# OGX360I-4CH_-_Middle_Man_P3_-_P4.net
KiCad netlist of a schematic drawn in EAGLE
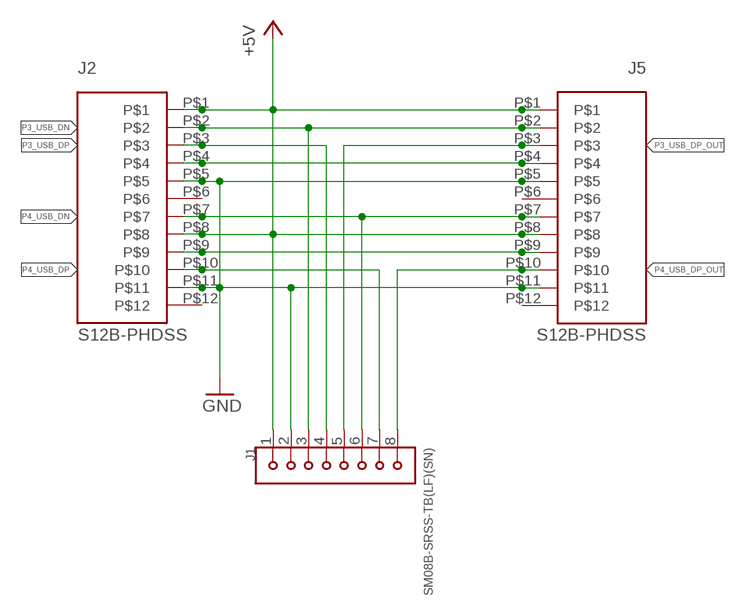
[diagram p0: schematic, sheet 1]

(export (version "E")
  (design (tool "Eeschema 10.0.6"))
  (components
    (comp (ref "J1")
      (value "SM08B-SRSS-TB(LF)(SN)")
      (footprint "eagle-import:JST_SM08B-SRSS-TB(LF)(SN)")
      (fields (field (name "MF") "JST Sales") (field (name "MP") "SM08B-SRSS-TB_LF__SN_"))
      (libsource (lib "eagle-import") (part "SM08B-SRSS-TB(LF)(SN)"))
    )
    (comp (ref "J2")
      (value "S12B-PHDSS")
      (footprint "eagle-import:S12B-PHDSS")
      (libsource (lib "eagle-import") (part "S12B-PHDSS"))
    )
    (comp (ref "J5")
      (value "S12B-PHDSS")
      (footprint "eagle-import:S12B-PHDSS")
      (libsource (lib "eagle-import") (part "S12B-PHDSS"))
    )
  )
  (nets
    (net (code "1") (name "+5V") (class "Default")
      (node (ref "J1") (pin "1") (pinfunction "1_1") (pintype "passive"))
      (node (ref "J2") (pin "P$1") (pinfunction "P$1_P$1") (pintype "bidirectional"))
      (node (ref "J2") (pin "P$8") (pinfunction "P$8_P$8") (pintype "bidirectional"))
      (node (ref "J5") (pin "P$1") (pinfunction "P$1_P$1") (pintype "bidirectional"))
      (node (ref "J5") (pin "P$8") (pinfunction "P$8_P$8") (pintype "bidirectional"))
    )
    (net (code "2") (name "GND") (class "Default")
      (node (ref "J1") (pin "2") (pinfunction "2_2") (pintype "passive"))
      (node (ref "J2") (pin "P$11") (pinfunction "P$11_P$11") (pintype "bidirectional"))
      (node (ref "J2") (pin "P$5") (pinfunction "P$5_P$5") (pintype "bidirectional"))
      (node (ref "J5") (pin "P$11") (pinfunction "P$11_P$11") (pintype "bidirectional"))
      (node (ref "J5") (pin "P$5") (pinfunction "P$5_P$5") (pintype "bidirectional"))
    )
    (net (code "3") (name "Net-(J2-PadP$4)") (class "Default")
      (node (ref "J2") (pin "P$4") (pinfunction "P$4_P$4") (pintype "bidirectional"))
      (node (ref "J5") (pin "P$4") (pinfunction "P$4_P$4") (pintype "bidirectional"))
    )
    (net (code "4") (name "Net-(J2-PadP$9)") (class "Default")
      (node (ref "J2") (pin "P$9") (pinfunction "P$9_P$9") (pintype "bidirectional"))
      (node (ref "J5") (pin "P$9") (pinfunction "P$9_P$9") (pintype "bidirectional"))
    )
    (net (code "5") (name "P3_USB_DN") (class "Default")
      (node (ref "J1") (pin "3") (pinfunction "3_3") (pintype "passive"))
      (node (ref "J2") (pin "P$2") (pinfunction "P$2_P$2") (pintype "bidirectional"))
      (node (ref "J5") (pin "P$2") (pinfunction "P$2_P$2") (pintype "bidirectional"))
    )
    (net (code "6") (name "P3_USB_DP") (class "Default")
      (node (ref "J1") (pin "4") (pinfunction "4_4") (pintype "passive"))
      (node (ref "J2") (pin "P$3") (pinfunction "P$3_P$3") (pintype "bidirectional"))
    )
    (net (code "7") (name "P3_USB_DP_OUT") (class "Default")
      (node (ref "J1") (pin "5") (pinfunction "5_5") (pintype "passive"))
      (node (ref "J5") (pin "P$3") (pinfunction "P$3_P$3") (pintype "bidirectional"))
    )
    (net (code "8") (name "P4_USB_DN") (class "Default")
      (node (ref "J1") (pin "6") (pinfunction "6_6") (pintype "passive"))
      (node (ref "J2") (pin "P$7") (pinfunction "P$7_P$7") (pintype "bidirectional"))
      (node (ref "J5") (pin "P$7") (pinfunction "P$7_P$7") (pintype "bidirectional"))
    )
    (net (code "9") (name "P4_USB_DP") (class "Default")
      (node (ref "J1") (pin "7") (pinfunction "7_7") (pintype "passive"))
      (node (ref "J2") (pin "P$10") (pinfunction "P$10_P$10") (pintype "bidirectional"))
    )
    (net (code "10") (name "P4_USB_DP_OUT") (class "Default")
      (node (ref "J1") (pin "8") (pinfunction "8_8") (pintype "passive"))
      (node (ref "J5") (pin "P$10") (pinfunction "P$10_P$10") (pintype "bidirectional"))
    )
    (net (code "11") (name "unconnected-(J2-PadP$6)") (class "Default")
      (node (ref "J2") (pin "P$6") (pinfunction "P$6_P$6") (pintype "bidirectional"))
    )
    (net (code "12") (name "unconnected-(J2-PadP$12)") (class "Default")
      (node (ref "J2") (pin "P$12") (pinfunction "P$12_P$12") (pintype "bidirectional"))
    )
    (net (code "13") (name "unconnected-(J5-PadP$6)") (class "Default")
      (node (ref "J5") (pin "P$6") (pinfunction "P$6_P$6") (pintype "bidirectional"))
    )
    (net (code "14") (name "unconnected-(J5-PadP$12)") (class "Default")
      (node (ref "J5") (pin "P$12") (pinfunction "P$12_P$12") (pintype "bidirectional"))
    )
  )
)
